# Sch2.net
KiCad netlist of a schematic drawn in Altium Designer
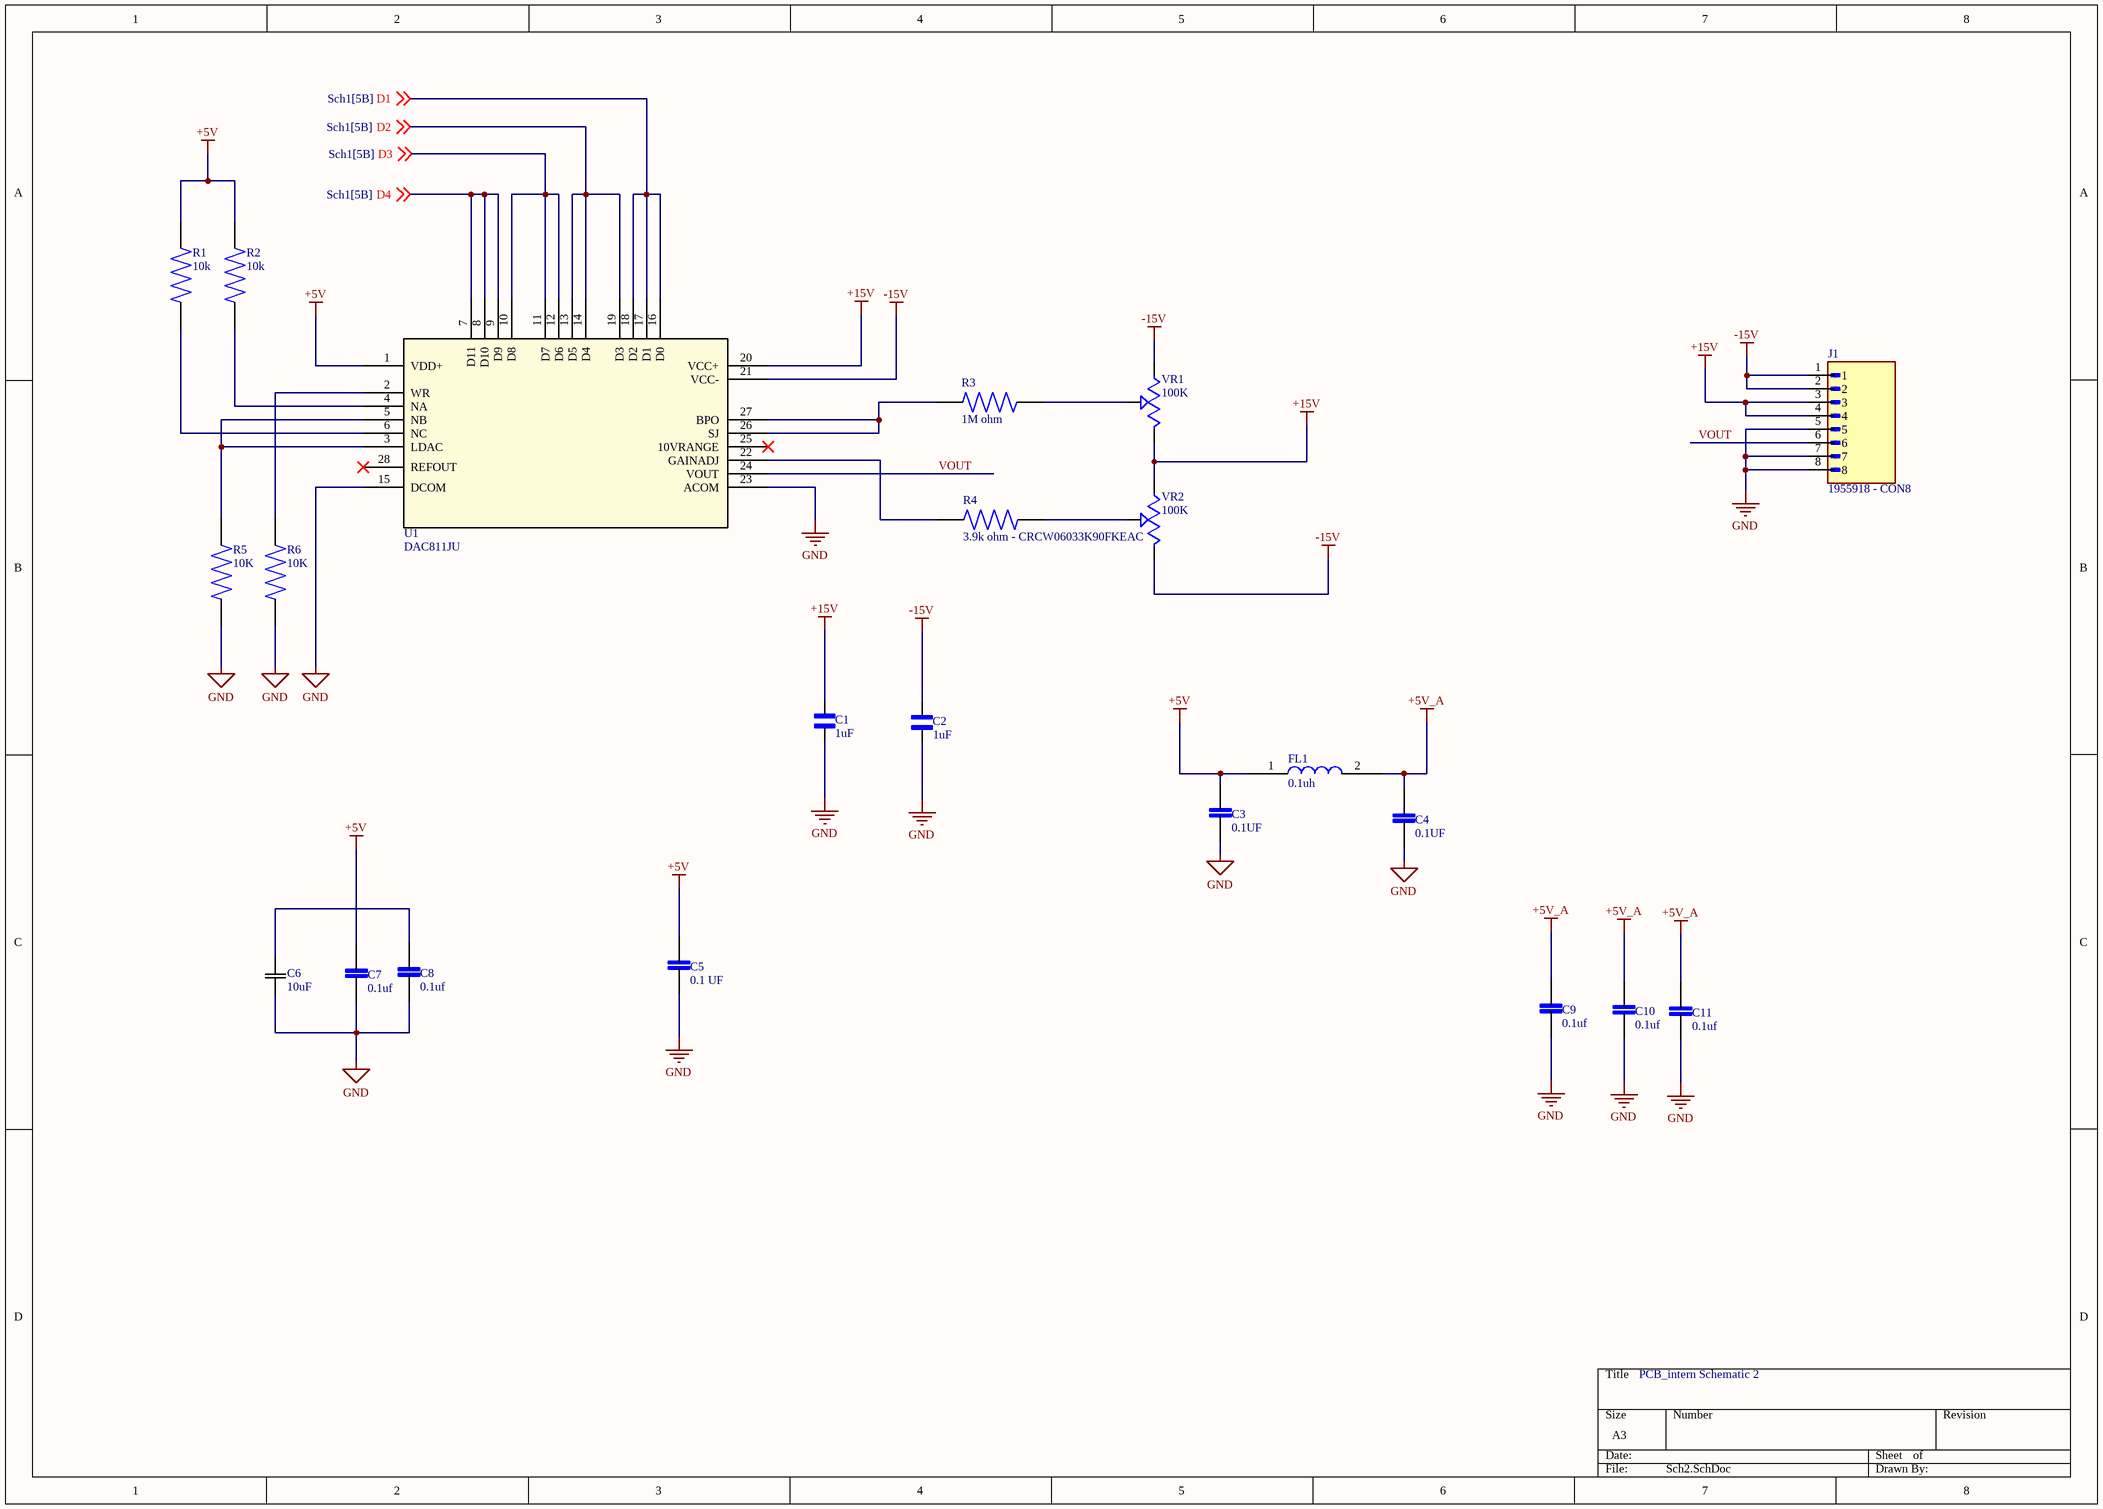
[diagram p0: Sch2.SchDoc]

(export (version "E")
  (design (tool "Eeschema 10.0.6"))
  (components
    (comp (ref "C1")
      (value "1uF")
      (footprint "VARC3216X85N")
      (description "Capacitor;Ceramic;Cap;.1 uF;Tol+10%;SMT;Vol-Rtg 50V;X7R;TR ¦ KEMET C1206C104K5RACTU")
      (fields (field (name "MF") "KEMET") (field (name "MP") "C1206C104K5RACTU"))
      (libsource (lib "Schlib3") (part "1uF - C1206C104K5RACTU"))
    )
    (comp (ref "C2")
      (value "1uF")
      (footprint "VARC3216X85N")
      (description "Capacitor;Ceramic;Cap;.1 uF;Tol+10%;SMT;Vol-Rtg 50V;X7R;TR ¦ KEMET C1206C104K5RACTU")
      (fields (field (name "MF") "KEMET") (field (name "MP") "C1206C104K5RACTU"))
      (libsource (lib "Schlib3") (part "1uF - C1206C104K5RACTU"))
    )
    (comp (ref "C3")
      (value "0.1UF")
      (footprint "CAPC1608X90")
      (description "0.1 ÂµF Â±10% 50V Ceramic Capacitor X7R 0603 (1608 Metric)")
      (fields (field (name "MF") "KEMET") (field (name "MP") "C0603C104K5RACTU"))
      (libsource (lib "Schlib3") (part "0.1uf - C0603C104K5RACTU"))
    )
    (comp (ref "C4")
      (value "0.1UF")
      (footprint "CAPC1608X90")
      (description "0.1 ÂµF Â±10% 50V Ceramic Capacitor X7R 0603 (1608 Metric)")
      (fields (field (name "MF") "KEMET") (field (name "MP") "C0603C104K5RACTU"))
      (libsource (lib "Schlib3") (part "0.1uf - C0603C104K5RACTU"))
    )
    (comp (ref "C5")
      (value "0.1 UF")
      (footprint "CAPC1608X90")
      (description "0.1 ÂµF Â±10% 50V Ceramic Capacitor X7R 0603 (1608 Metric)")
      (fields (field (name "MF") "KEMET") (field (name "MP") "C0603C104K5RACTU"))
      (libsource (lib "Schlib3") (part "0.1uf - C0603C104K5RACTU"))
    )
    (comp (ref "C6")
      (value "10uF")
      (footprint "CAP_TCJ-C-2312_KAV")
      (description "Description")
      (fields
        (field (name "MANUFACTURER_PART_NUMBER") "TCJC106M035R0200E")
        (field (name "COPYRIGHT") "Copyright (C) 2025 Ultra Librarian. All rights reserved.")
      )
      (libsource (lib "Schlib3") (part "10UF - TCJC106M035R0200E"))
    )
    (comp (ref "C7")
      (value "0.1uf")
      (footprint "CAPC1608X90")
      (description "0.1 ÂµF Â±10% 50V Ceramic Capacitor X7R 0603 (1608 Metric)")
      (fields (field (name "MF") "KEMET") (field (name "MP") "C0603C104K5RACTU"))
      (libsource (lib "Schlib3") (part "0.1uf - C0603C104K5RACTU"))
    )
    (comp (ref "C8")
      (value "0.1uf")
      (footprint "CAPC1608X90")
      (description "0.1 ÂµF Â±10% 50V Ceramic Capacitor X7R 0603 (1608 Metric)")
      (fields (field (name "MF") "KEMET") (field (name "MP") "C0603C104K5RACTU"))
      (libsource (lib "Schlib3") (part "0.1uf - C0603C104K5RACTU"))
    )
    (comp (ref "C9")
      (value "0.1uf")
      (footprint "CAPC1608X90")
      (description "0.1 ÂµF Â±10% 50V Ceramic Capacitor X7R 0603 (1608 Metric)")
      (fields (field (name "MF") "KEMET") (field (name "MP") "C0603C104K5RACTU"))
      (libsource (lib "Schlib3") (part "0.1uf - C0603C104K5RACTU"))
    )
    (comp (ref "C10")
      (value "0.1uf")
      (footprint "CAPC1608X90")
      (description "0.1 ÂµF Â±10% 50V Ceramic Capacitor X7R 0603 (1608 Metric)")
      (fields (field (name "MF") "KEMET") (field (name "MP") "C0603C104K5RACTU"))
      (libsource (lib "Schlib3") (part "0.1uf - C0603C104K5RACTU"))
    )
    (comp (ref "C11")
      (value "0.1uf")
      (footprint "CAPC1608X90")
      (description "0.1 ÂµF Â±10% 50V Ceramic Capacitor X7R 0603 (1608 Metric)")
      (fields (field (name "MF") "KEMET") (field (name "MP") "C0603C104K5RACTU"))
      (libsource (lib "Schlib3") (part "0.1uf - C0603C104K5RACTU"))
    )
    (comp (ref "FL1")
      (value "0.1uh")
      (footprint "BEADC1608X95N")
      (description "0.1uHz 1 - Ferrite Bead 0603 (1608 Metric) 500mA 380mOhm")
      (fields (field (name "MF") "Murata") (field (name "MP") "BLM18AG601SN1D"))
      (libsource (lib "Schlib2") (part "0.1uh-BLM18AG601SN1D"))
    )
    (comp (ref "J1")
      (value "1955918 - CON8")
      (footprint "PHOENIX_1955918")
      (fields (field (name "MP") "1955918"))
      (libsource (lib "Schlib3") (part "1955918 - CON8"))
    )
    (comp (ref "R1")
      (value "10k")
      (footprint "RESC1508X50N")
      (fields (field (name "MF") "Vishay") (field (name "MP") "CRCW060310K0FKEA"))
      (libsource (lib "Schlib3") (part "10k ohm - CRCW060310K0FKEA"))
    )
    (comp (ref "R2")
      (value "10k")
      (footprint "RESC1508X50N")
      (fields (field (name "MF") "Vishay") (field (name "MP") "CRCW060310K0FKEA"))
      (libsource (lib "Schlib3") (part "10k ohm - CRCW060310K0FKEA"))
    )
    (comp (ref "R3")
      (value "1M ohm")
      (footprint "RESC1508X50N")
      (fields (field (name "MF") "Vishay") (field (name "MP") "CRCW06031M00FKEA"))
      (libsource (lib "Schlib3") (part "1MHz - CRCW06031M00FKEA"))
    )
    (comp (ref "R4")
      (value "3.9k ohm - CRCW06033K90FKEAC")
      (footprint "PCB_LIB:RESC1608X55N")
      (fields (field (name "MP") "CRCW06033K90FKEAC"))
      (libsource (lib "Schlib2") (part "3.9k ohm - CRCW06033K90FKEAC"))
    )
    (comp (ref "R5")
      (value "10K")
      (footprint "RESC1508X50N")
      (fields (field (name "MF") "Vishay") (field (name "MP") "CRCW060310K0FKEA"))
      (libsource (lib "Schlib3") (part "10k ohm - CRCW060310K0FKEA"))
    )
    (comp (ref "R6")
      (value "10K")
      (footprint "RESC1508X50N")
      (fields (field (name "MF") "Vishay") (field (name "MP") "CRCW060310K0FKEA"))
      (libsource (lib "Schlib3") (part "10k ohm - CRCW060310K0FKEA"))
    )
    (comp (ref "U1")
      (value "DAC811JU")
      (footprint "DW28")
      (description "12-bit Digital-to-Analog Converter w/Parallel Interface 28-SOIC 0 to 70")
      (fields (field (name "COPYRIGHT") "Copyright (C) 2026 Ultra Librarian. All rights reserved."))
      (libsource (lib "Schlib3") (part "U3 - DAC811JU"))
    )
    (comp (ref "VR1")
      (value "100K")
      (footprint "TRIM_3266W-1-104LF:TRIM_3266W-1-104LF")
      (description "100 kOhms 0.25W, 1/4W PC Pins Through Hole Trimmer Potentiometer Cermet 12 Turn Top Adjustment")
      (fields (field (name "MP") "3266W-1-104LF") (field (name "MF") "Bourns"))
      (libsource (lib "Schlib3") (part "100K variable res - 3266W-1-104LF"))
    )
    (comp (ref "VR2")
      (value "100K")
      (footprint "TRIM_3266W-1-104LF:TRIM_3266W-1-104LF")
      (description "100 kOhms 0.25W, 1/4W PC Pins Through Hole Trimmer Potentiometer Cermet 12 Turn Top Adjustment")
      (fields (field (name "MP") "3266W-1-104LF") (field (name "MF") "Bourns"))
      (libsource (lib "Schlib3") (part "100K variable res - 3266W-1-104LF"))
    )
  )
  (nets
    (net (code "1") (name "+5V") (class "Default")
      (node (ref "C3") (pin "2") (pinfunction "2_2") (pintype "passive"))
      (node (ref "C5") (pin "2") (pinfunction "2_2") (pintype "passive"))
      (node (ref "C7") (pin "2") (pinfunction "2_2") (pintype "passive"))
      (node (ref "FL1") (pin "1") (pintype "passive"))
      (node (ref "R1") (pin "2") (pinfunction "2_2") (pintype "passive"))
      (node (ref "R2") (pin "2") (pinfunction "2_2") (pintype "passive"))
      (node (ref "U1") (pin "1") (pinfunction "VDD+_1") (pintype "power_in"))
    )
    (net (code "2") (name "+5V_A") (class "Default")
      (node (ref "C10") (pin "2") (pinfunction "2_2") (pintype "passive"))
      (node (ref "C11") (pin "2") (pinfunction "2_2") (pintype "passive"))
      (node (ref "C4") (pin "2") (pinfunction "2_2") (pintype "passive"))
      (node (ref "C9") (pin "2") (pinfunction "2_2") (pintype "passive"))
      (node (ref "FL1") (pin "2") (pintype "passive"))
    )
    (net (code "3") (name "+15V") (class "Default")
      (node (ref "C1") (pin "1") (pinfunction "1_1") (pintype "passive"))
      (node (ref "J1") (pin "3") (pinfunction "3_3") (pintype "passive"))
      (node (ref "J1") (pin "4") (pinfunction "4_4") (pintype "passive"))
      (node (ref "U1") (pin "20") (pinfunction "VCC+_20") (pintype "power_in"))
      (node (ref "VR1") (pin "3") (pinfunction "CW_3") (pintype "passive"))
      (node (ref "VR2") (pin "1") (pinfunction "CCW_1") (pintype "passive"))
    )
    (net (code "4") (name "-15V") (class "Default")
      (node (ref "C2") (pin "1") (pinfunction "1_1") (pintype "passive"))
      (node (ref "J1") (pin "1") (pinfunction "1_1") (pintype "passive"))
      (node (ref "J1") (pin "2") (pinfunction "2_2") (pintype "passive"))
      (node (ref "U1") (pin "21") (pinfunction "VCC-_21") (pintype "power_in"))
      (node (ref "VR1") (pin "1") (pinfunction "CCW_1") (pintype "passive"))
      (node (ref "VR2") (pin "3") (pinfunction "CW_3") (pintype "passive"))
    )
    (net (code "5") (name "/VOUT") (class "Default")
      (node (ref "J1") (pin "6") (pinfunction "6_6") (pintype "passive"))
      (node (ref "U1") (pin "24") (pinfunction "VOUT_24") (pintype "passive"))
    )
    (net (code "6") (name "D1") (class "Default")
      (node (ref "U1") (pin "16") (pinfunction "D0_16") (pintype "passive"))
      (node (ref "U1") (pin "17") (pinfunction "D1_17") (pintype "passive"))
      (node (ref "U1") (pin "18") (pinfunction "D2_18") (pintype "passive"))
    )
    (net (code "7") (name "D2") (class "Default")
      (node (ref "U1") (pin "13") (pinfunction "D5_13") (pintype "passive"))
      (node (ref "U1") (pin "14") (pinfunction "D4_14") (pintype "passive"))
      (node (ref "U1") (pin "19") (pinfunction "D3_19") (pintype "passive"))
    )
    (net (code "8") (name "D3") (class "Default")
      (node (ref "U1") (pin "10") (pinfunction "D8_10") (pintype "passive"))
      (node (ref "U1") (pin "11") (pinfunction "D7_11") (pintype "passive"))
      (node (ref "U1") (pin "12") (pinfunction "D6_12") (pintype "passive"))
    )
    (net (code "9") (name "D4") (class "Default")
      (node (ref "U1") (pin "7") (pinfunction "D11_7") (pintype "passive"))
      (node (ref "U1") (pin "8") (pinfunction "D10_8") (pintype "passive"))
      (node (ref "U1") (pin "9") (pinfunction "D9_9") (pintype "passive"))
    )
    (net (code "10") (name "GND") (class "Default")
      (node (ref "C1") (pin "2") (pinfunction "2_2") (pintype "passive"))
      (node (ref "C10") (pin "1") (pinfunction "1_1") (pintype "passive"))
      (node (ref "C11") (pin "1") (pinfunction "1_1") (pintype "passive"))
      (node (ref "C2") (pin "2") (pinfunction "2_2") (pintype "passive"))
      (node (ref "C3") (pin "1") (pinfunction "1_1") (pintype "passive"))
      (node (ref "C4") (pin "1") (pinfunction "1_1") (pintype "passive"))
      (node (ref "C5") (pin "1") (pinfunction "1_1") (pintype "passive"))
      (node (ref "C6") (pin "1") (pinfunction "1_1") (pintype "passive"))
      (node (ref "C7") (pin "1") (pinfunction "1_1") (pintype "passive"))
      (node (ref "C8") (pin "1") (pinfunction "1_1") (pintype "passive"))
      (node (ref "C9") (pin "1") (pinfunction "1_1") (pintype "passive"))
      (node (ref "J1") (pin "5") (pinfunction "5_5") (pintype "passive"))
      (node (ref "J1") (pin "7") (pinfunction "7_7") (pintype "passive"))
      (node (ref "J1") (pin "8") (pinfunction "8_8") (pintype "passive"))
      (node (ref "R5") (pin "1") (pinfunction "1_1") (pintype "passive"))
      (node (ref "R6") (pin "1") (pinfunction "1_1") (pintype "passive"))
      (node (ref "U1") (pin "15") (pinfunction "DCOM_15") (pintype "power_in"))
      (node (ref "U1") (pin "23") (pinfunction "ACOM_23") (pintype "power_in"))
    )
    (net (code "11") (name "Net-(C6-Pad2)") (class "Default")
      (node (ref "C6") (pin "2") (pinfunction "2_2") (pintype "passive"))
      (node (ref "C8") (pin "2") (pinfunction "2_2") (pintype "passive"))
    )
    (net (code "12") (name "Net-(U1-BPO)") (class "Default")
      (node (ref "R3") (pin "1") (pinfunction "1_1") (pintype "passive"))
      (node (ref "U1") (pin "26") (pinfunction "SJ_26") (pintype "passive"))
      (node (ref "U1") (pin "27") (pinfunction "BPO_27") (pintype "passive"))
    )
    (net (code "13") (name "Net-(U1-GAINADJ)") (class "Default")
      (node (ref "R4") (pin "1") (pinfunction "1_1") (pintype "passive"))
      (node (ref "U1") (pin "22") (pinfunction "GAINADJ_22") (pintype "passive"))
    )
    (net (code "14") (name "Net-(U1-LDAC)") (class "Default")
      (node (ref "R5") (pin "2") (pinfunction "2_2") (pintype "passive"))
      (node (ref "U1") (pin "3") (pinfunction "LDAC_3") (pintype "passive"))
      (node (ref "U1") (pin "5") (pinfunction "NB_5") (pintype "passive"))
    )
    (net (code "15") (name "Net-(U1-NA)") (class "Default")
      (node (ref "R2") (pin "1") (pinfunction "1_1") (pintype "passive"))
      (node (ref "U1") (pin "4") (pinfunction "NA_4") (pintype "passive"))
    )
    (net (code "16") (name "Net-(U1-NC)") (class "Default")
      (node (ref "R1") (pin "1") (pinfunction "1_1") (pintype "passive"))
      (node (ref "U1") (pin "6") (pinfunction "NC_6") (pintype "passive"))
    )
    (net (code "17") (name "Net-(U1-WR)") (class "Default")
      (node (ref "R6") (pin "2") (pinfunction "2_2") (pintype "passive"))
      (node (ref "U1") (pin "2") (pinfunction "WR_2") (pintype "passive"))
    )
    (net (code "18") (name "Net-(VR1-WIPER)") (class "Default")
      (node (ref "R3") (pin "2") (pinfunction "2_2") (pintype "passive"))
      (node (ref "VR1") (pin "2") (pinfunction "WIPER_2") (pintype "passive"))
    )
    (net (code "19") (name "Net-(VR2-WIPER)") (class "Default")
      (node (ref "R4") (pin "2") (pinfunction "2_2") (pintype "passive"))
      (node (ref "VR2") (pin "2") (pinfunction "WIPER_2") (pintype "passive"))
    )
    (net (code "20") (name "unconnected-(U1-10VRANGE-Pad25)") (class "Default")
      (node (ref "U1") (pin "25") (pinfunction "10VRANGE_25") (pintype "power_in+no_connect"))
    )
    (net (code "21") (name "unconnected-(U1-REFOUT-Pad28)") (class "Default")
      (node (ref "U1") (pin "28") (pinfunction "REFOUT_28") (pintype "passive+no_connect"))
    )
  )
)
